# Power.net
KiCad netlist of a schematic drawn in Altium Designer
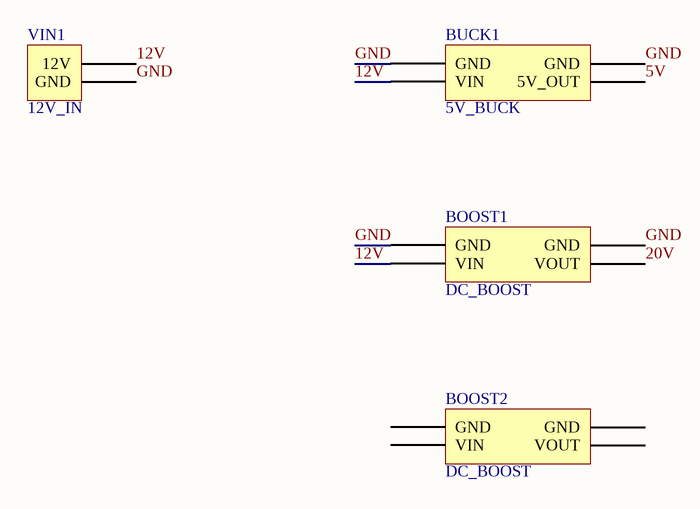
[diagram p0: Power.SchDoc]

(export (version "E")
  (design (tool "Eeschema 10.0.6"))
  (components
    (comp (ref "BOOST1")
      (value "DC_BOOST")
      (description "Boost converter for 20V power for pressure transducers")
      (libsource (lib "components") (part "DC_BOOST"))
    )
    (comp (ref "BOOST2") (value "DC_BOOST") (libsource (lib "components") (part "DC_BOOST")))
    (comp (ref "BUCK1") (value "5V_BUCK") (libsource (lib "components") (part "5V_BUCK")))
    (comp (ref "VIN1") (value "12V_IN") (libsource (lib "components") (part "12V_IN")))
  )
  (nets
    (net (code "1") (name "/5V") (class "Default")
      (node (ref "BUCK1") (pin "3") (pinfunction "5V_OUT_3") (pintype "passive"))
    )
    (net (code "2") (name "/12V") (class "Default")
      (node (ref "BOOST1") (pin "2") (pinfunction "VIN_2") (pintype "passive"))
      (node (ref "BUCK1") (pin "2") (pinfunction "VIN_2") (pintype "passive"))
      (node (ref "VIN1") (pin "2") (pinfunction "12V_2") (pintype "passive"))
    )
    (net (code "3") (name "/20V") (class "Default")
      (node (ref "BOOST1") (pin "3") (pinfunction "VOUT_3") (pintype "passive"))
    )
    (net (code "4") (name "/GND") (class "Default")
      (node (ref "BOOST1") (pin "1") (pinfunction "GND_1") (pintype "passive"))
      (node (ref "BOOST1") (pin "4") (pinfunction "GND_4") (pintype "passive"))
      (node (ref "BUCK1") (pin "1") (pinfunction "GND_1") (pintype "passive"))
      (node (ref "BUCK1") (pin "4") (pinfunction "GND_4") (pintype "passive"))
      (node (ref "VIN1") (pin "1") (pinfunction "GND_1") (pintype "passive"))
    )
    (net (code "5") (name "unconnected-(BOOST2-GND-Pad1)") (class "Default")
      (node (ref "BOOST2") (pin "1") (pinfunction "GND_1") (pintype "passive"))
    )
    (net (code "6") (name "unconnected-(BOOST2-GND-Pad4)") (class "Default")
      (node (ref "BOOST2") (pin "4") (pinfunction "GND_4") (pintype "passive"))
    )
    (net (code "7") (name "unconnected-(BOOST2-VIN-Pad2)") (class "Default")
      (node (ref "BOOST2") (pin "2") (pinfunction "VIN_2") (pintype "passive"))
    )
    (net (code "8") (name "unconnected-(BOOST2-VOUT-Pad3)") (class "Default")
      (node (ref "BOOST2") (pin "3") (pinfunction "VOUT_3") (pintype "passive"))
    )
  )
)
